# 3_UART_RS232_Conversion.net
KiCad netlist of a schematic drawn in Altium Designer
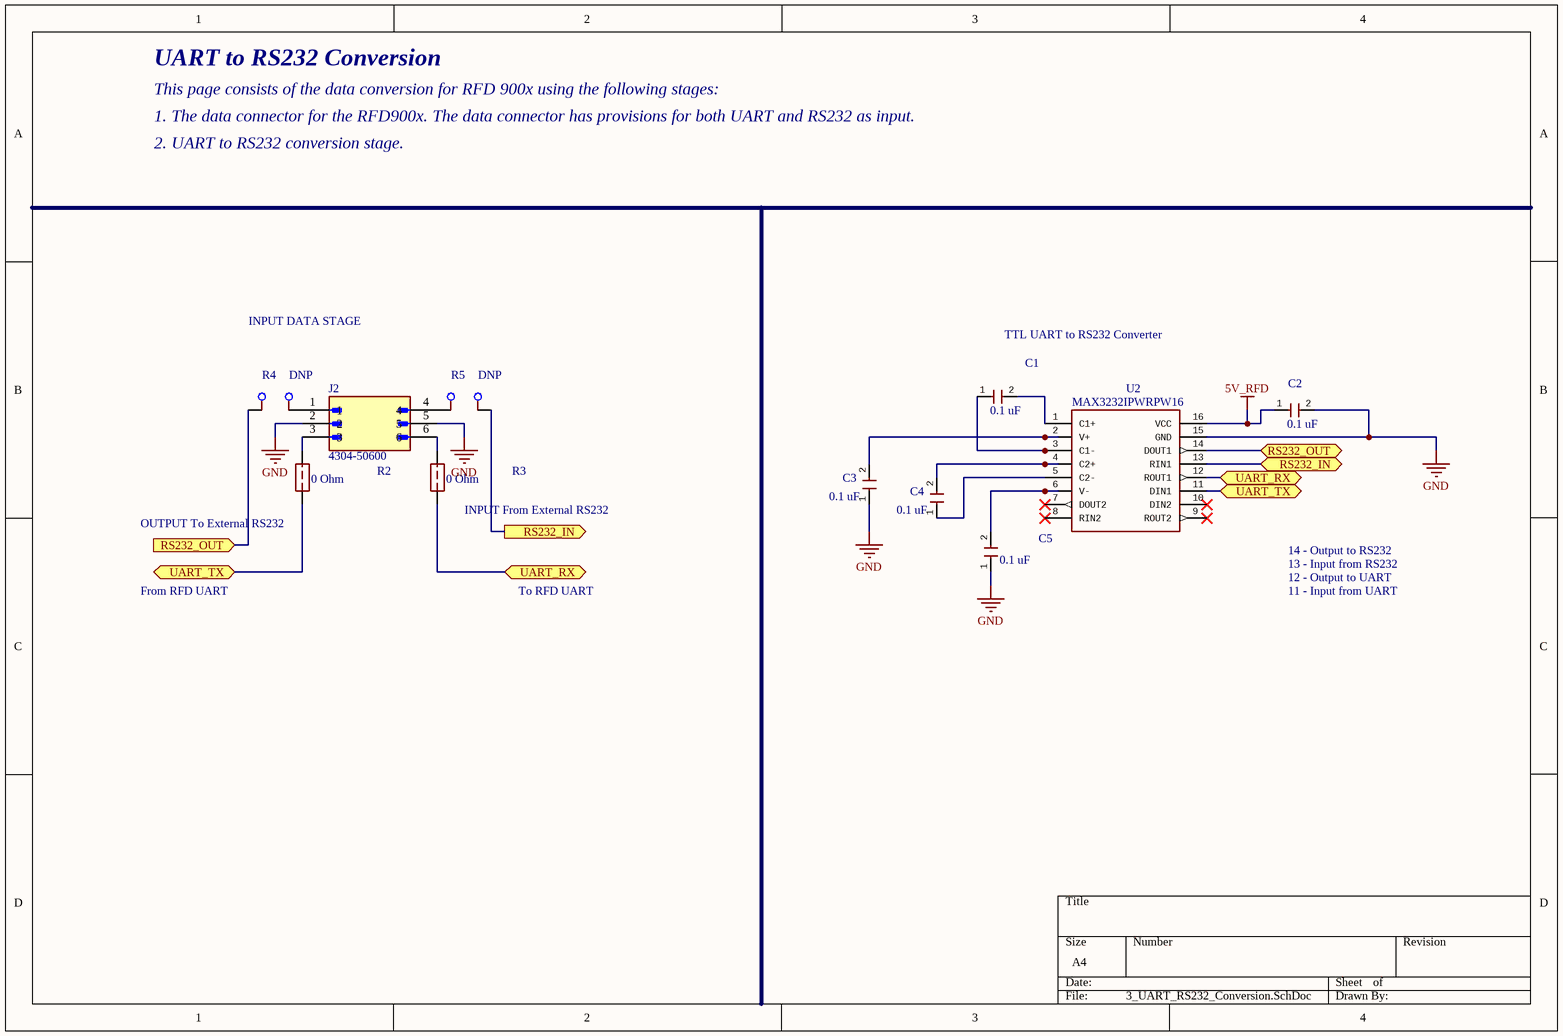
[diagram p0: 3_UART_RS232_Conversion.SchDoc]

(export (version "E")
  (design (tool "Eeschema 10.0.6"))
  (components
    (comp (ref "C1")
      (value "0.1 uF")
      (footprint "CAP_0603")
      (description "Cap Ceramic 0.1uF 50V 0603")
      (fields (field (name "PARTNUMBER") "CL10B104KB8NNNC"))
      (libsource (lib "Passives") (part "CL10B104KB8NNNC"))
    )
    (comp (ref "C2")
      (value "0.1 uF")
      (footprint "CAP_0603")
      (description "Cap Ceramic 0.1uF 50V 0603")
      (fields (field (name "PARTNUMBER") "CL10B104KB8NNNC"))
      (libsource (lib "Passives") (part "CL10B104KB8NNNC"))
    )
    (comp (ref "C3")
      (value "0.1 uF")
      (footprint "CAP_0603")
      (description "Cap Ceramic 0.1uF 50V 0603")
      (fields (field (name "PARTNUMBER") "CL10B104KB8NNNC"))
      (libsource (lib "Passives") (part "CL10B104KB8NNNC"))
    )
    (comp (ref "C4")
      (value "0.1 uF")
      (footprint "CAP_0603")
      (description "Cap Ceramic 0.1uF 50V 0603")
      (fields (field (name "PARTNUMBER") "CL10B104KB8NNNC"))
      (libsource (lib "Passives") (part "CL10B104KB8NNNC"))
    )
    (comp (ref "C5")
      (value "0.1 uF")
      (footprint "CAP_0603")
      (description "Cap Ceramic 0.1uF 50V 0603")
      (fields (field (name "PARTNUMBER") "CL10B104KB8NNNC"))
      (libsource (lib "Passives") (part "CL10B104KB8NNNC"))
    )
    (comp (ref "J2")
      (value "4304-50600")
      (footprint "MOLEX_MICRO-6POS")
      (description "Molex Microfit 6POS")
      (fields (field (name "PARTNUMBER") "430450600") (field (name "MANUFACTURER") "Molex"))
      (libsource (lib "Connectors") (part "43045-0600"))
    )
    (comp (ref "R2")
      (value "0 Ohm")
      (footprint "RES_0603")
      (description "Res 0Ohm 1/10W 0603")
      (fields (field (name "PARTNUMBER") "ERJ3GEY0R00V"))
      (libsource (lib "Passives") (part "ERJ3GEY0R00V"))
    )
    (comp (ref "R3")
      (value "0 Ohm")
      (footprint "RES_0603")
      (description "Res 0Ohm 1/10W 0603")
      (fields (field (name "PARTNUMBER") "ERJ3GEY0R00V"))
      (libsource (lib "Passives") (part "ERJ3GEY0R00V"))
    )
    (comp (ref "R4")
      (value "DNP")
      (footprint "RES_0603_DNP")
      (description "0603 RES Footprint")
      (fields (field (name "Comment") "0603 Resistor DNP"))
      (libsource (lib "Miscellaneous") (part "RES_0603"))
    )
    (comp (ref "R5")
      (value "DNP")
      (footprint "RES_0603_DNP")
      (description "0603 RES Footprint")
      (fields (field (name "Comment") "0603 Resistor DNP"))
      (libsource (lib "Miscellaneous") (part "RES_0603"))
    )
    (comp (ref "U2")
      (value "MAX3232IPWRPW16")
      (footprint "INTERFACE_TSSOP-16")
      (description "Transceiver 3.3~5V 250Kbps")
      (fields (field (name "MANUFACTURER") "Texas Instruments") (field (name "PARTNUMBER") "MAX3232IPWR"))
      (libsource (lib "InterfaceICs") (part "MAX3232IPWRPW16"))
    )
  )
  (nets
    (net (code "1") (name "/RS232_IN") (class "Default")
      (node (ref "R5") (pin "2") (pinfunction "2_2") (pintype "passive"))
      (node (ref "U2") (pin "13") (pinfunction "RIN1_13") (pintype "passive"))
    )
    (net (code "2") (name "/RS232_OUT") (class "Default")
      (node (ref "R4") (pin "1") (pinfunction "1_1") (pintype "passive"))
      (node (ref "U2") (pin "14") (pinfunction "DOUT1_14") (pintype "output"))
    )
    (net (code "3") (name "/UART_RX") (class "Default")
      (node (ref "R3") (pin "1") (pinfunction "1_1") (pintype "passive"))
      (node (ref "U2") (pin "12") (pinfunction "ROUT1_12") (pintype "output"))
    )
    (net (code "4") (name "/UART_TX") (class "Default")
      (node (ref "R2") (pin "1") (pinfunction "1_1") (pintype "passive"))
      (node (ref "U2") (pin "11") (pinfunction "DIN1_11") (pintype "passive"))
    )
    (net (code "5") (name "5V_RFD") (class "Default")
      (node (ref "C2") (pin "1") (pinfunction "1_1") (pintype "passive"))
      (node (ref "U2") (pin "16") (pinfunction "VCC_16") (pintype "power_in"))
    )
    (net (code "6") (name "GND") (class "Default")
      (node (ref "C2") (pin "2") (pinfunction "2_2") (pintype "passive"))
      (node (ref "C3") (pin "1") (pinfunction "1_1") (pintype "passive"))
      (node (ref "C5") (pin "1") (pinfunction "1_1") (pintype "passive"))
      (node (ref "J2") (pin "2") (pinfunction "2_2") (pintype "passive"))
      (node (ref "J2") (pin "5") (pinfunction "5_5") (pintype "passive"))
      (node (ref "U2") (pin "15") (pinfunction "GND_15") (pintype "power_in"))
    )
    (net (code "7") (name "Net-(J2-Pad1)") (class "Default")
      (node (ref "J2") (pin "1") (pinfunction "1_1") (pintype "passive"))
      (node (ref "R4") (pin "2") (pinfunction "2_2") (pintype "passive"))
    )
    (net (code "8") (name "Net-(J2-Pad3)") (class "Default")
      (node (ref "J2") (pin "3") (pinfunction "3_3") (pintype "passive"))
      (node (ref "R2") (pin "2") (pinfunction "2_2") (pintype "passive"))
    )
    (net (code "9") (name "Net-(J2-Pad4)") (class "Default")
      (node (ref "J2") (pin "4") (pinfunction "4_4") (pintype "passive"))
      (node (ref "R5") (pin "1") (pinfunction "1_1") (pintype "passive"))
    )
    (net (code "10") (name "Net-(J2-Pad6)") (class "Default")
      (node (ref "J2") (pin "6") (pinfunction "6_6") (pintype "passive"))
      (node (ref "R3") (pin "2") (pinfunction "2_2") (pintype "passive"))
    )
    (net (code "11") (name "Net-(U2-C1+)") (class "Default")
      (node (ref "C1") (pin "2") (pinfunction "2_2") (pintype "passive"))
      (node (ref "U2") (pin "1") (pinfunction "C1+_1") (pintype "passive"))
    )
    (net (code "12") (name "Net-(U2-C1-)") (class "Default")
      (node (ref "C1") (pin "1") (pinfunction "1_1") (pintype "passive"))
      (node (ref "U2") (pin "3") (pinfunction "C1-_3") (pintype "passive"))
    )
    (net (code "13") (name "Net-(U2-C2+)") (class "Default")
      (node (ref "C4") (pin "2") (pinfunction "2_2") (pintype "passive"))
      (node (ref "U2") (pin "4") (pinfunction "C2+_4") (pintype "passive"))
    )
    (net (code "14") (name "Net-(U2-C2-)") (class "Default")
      (node (ref "C4") (pin "1") (pinfunction "1_1") (pintype "passive"))
      (node (ref "U2") (pin "5") (pinfunction "C2-_5") (pintype "passive"))
    )
    (net (code "15") (name "Net-(U2-V+)") (class "Default")
      (node (ref "C3") (pin "2") (pinfunction "2_2") (pintype "passive"))
      (node (ref "U2") (pin "2") (pinfunction "V+_2") (pintype "power_in"))
    )
    (net (code "16") (name "Net-(U2-V-)") (class "Default")
      (node (ref "C5") (pin "2") (pinfunction "2_2") (pintype "passive"))
      (node (ref "U2") (pin "6") (pinfunction "V-_6") (pintype "power_in"))
    )
    (net (code "17") (name "unconnected-(U2-DIN2-Pad10)") (class "Default")
      (node (ref "U2") (pin "10") (pinfunction "DIN2_10") (pintype "passive+no_connect"))
    )
    (net (code "18") (name "unconnected-(U2-DOUT2-Pad7)") (class "Default")
      (node (ref "U2") (pin "7") (pinfunction "DOUT2_7") (pintype "output+no_connect"))
    )
    (net (code "19") (name "unconnected-(U2-RIN2-Pad8)") (class "Default")
      (node (ref "U2") (pin "8") (pinfunction "RIN2_8") (pintype "passive+no_connect"))
    )
    (net (code "20") (name "unconnected-(U2-ROUT2-Pad9)") (class "Default")
      (node (ref "U2") (pin "9") (pinfunction "ROUT2_9") (pintype "output+no_connect"))
    )
  )
)
